# SCH_Andrew_s-NFC-Card_2024-04-21.net
KiCad netlist of a schematic drawn in EasyEDA
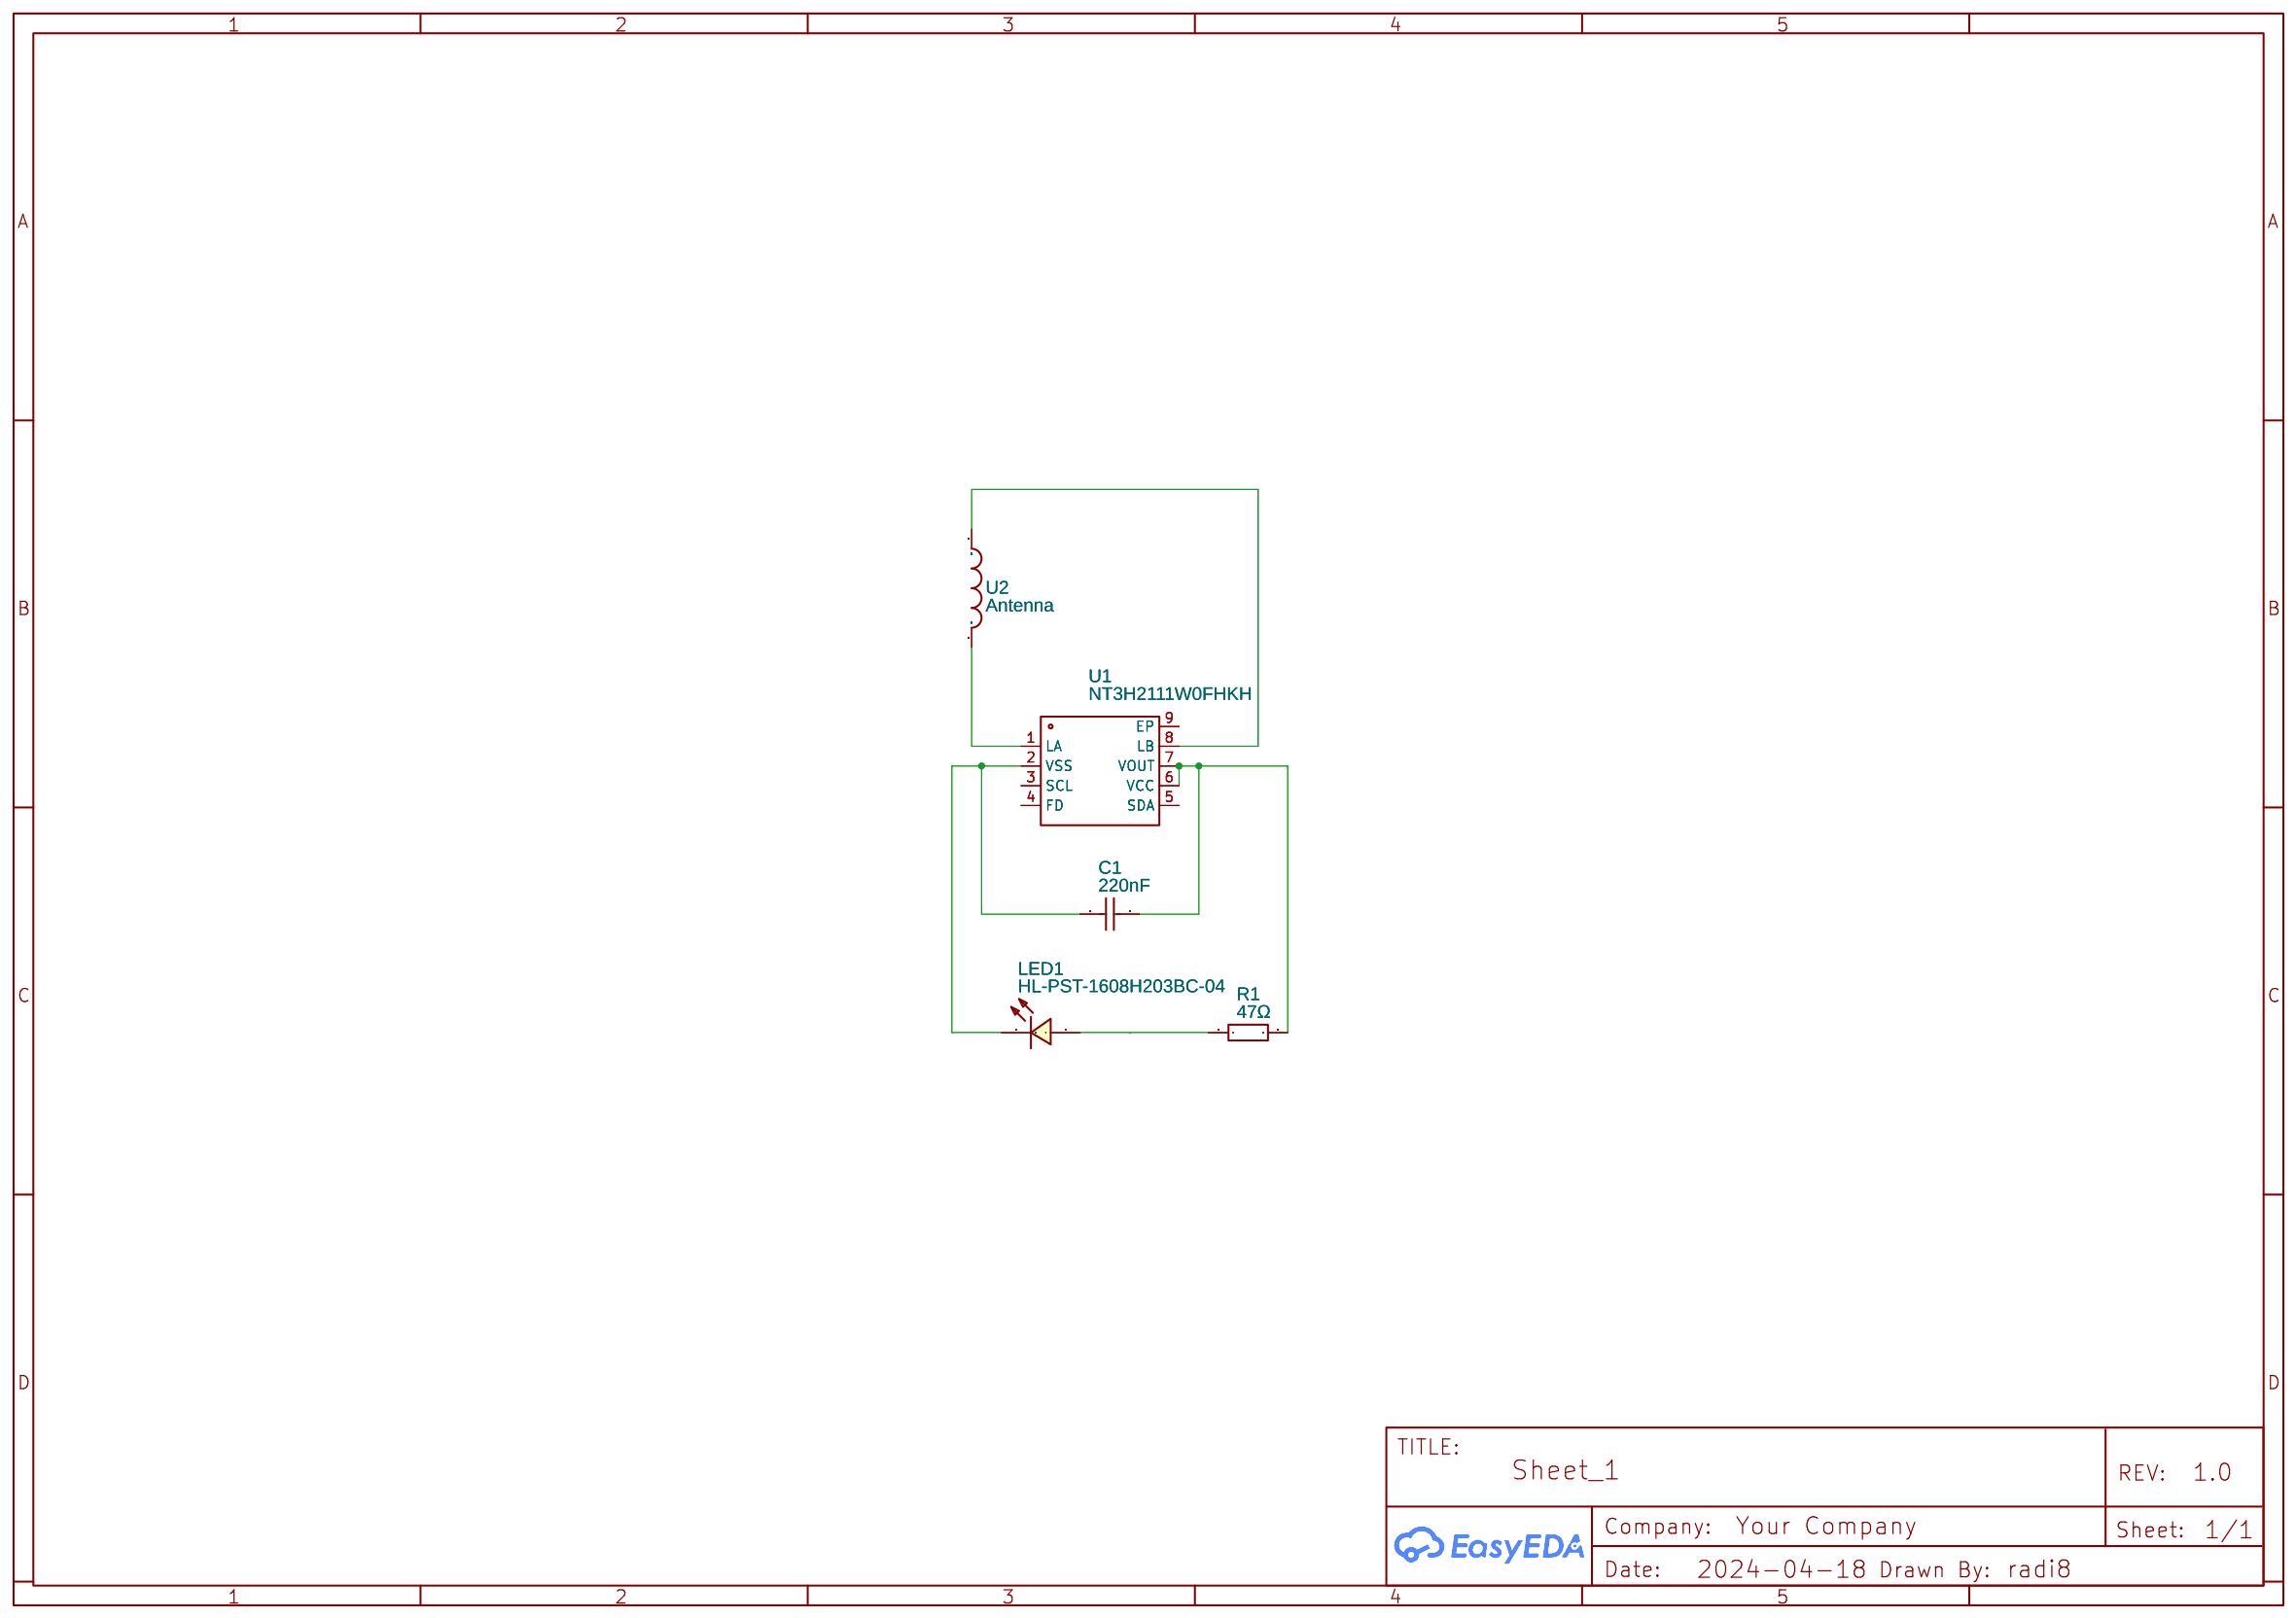
[diagram p0: schematic sheet]

(export (version "E")
  (design (tool "Eeschema 10.0.6"))
  (components
    (comp (ref "C1")
      (value "220nF")
      (fields
        (field (name "Manufacturer Part") "CL10B224KA8NNNC")
        (field (name "Manufacturer") "SAMSUNG(三星)")
      )
      (libsource (lib "") (part "CL10B224KA8NNNC"))
    )
    (comp (ref "LED1")
      (value "HL-PST-1608H203BC-04")
      (fields (field (name "Manufacturer") "HONGLITRONIC(鸿利光电)"))
      (libsource (lib "") (part "HL-PST-1608H203BC-04"))
    )
    (comp (ref "R1")
      (value "47Ω")
      (fields
        (field (name "Manufacturer Part") "0603WAF470JT5E")
        (field (name "Manufacturer") "UNI-ROYAL(厚声)")
      )
      (libsource (lib "") (part "0603WAF470JT5E"))
    )
    (comp (ref "U1")
      (value "NT3H2111W0FHKH")
      (fields (field (name "Manufacturer") "NXP(恩智浦)"))
      (libsource (lib "") (part "NT3H2111W0FHKH"))
    )
    (comp (ref "U2") (value "Antenna") (libsource (lib "") (part "Antenna")))
  )
  (nets
    (net (code "1") (name "Net-(LED1-A)") (class "Default")
      (node (ref "LED1") (pin "2") (pinfunction "A_2") (pintype "unspecified"))
      (node (ref "R1") (pin "1") (pinfunction "1_1") (pintype "input"))
    )
    (net (code "2") (name "Net-(LED1-C)") (class "Default")
      (node (ref "C1") (pin "1") (pinfunction "1_1") (pintype "input"))
      (node (ref "LED1") (pin "1") (pinfunction "C_1") (pintype "unspecified"))
      (node (ref "U1") (pin "2") (pinfunction "VSS_2") (pintype "unspecified"))
    )
    (net (code "3") (name "Net-(U1-LA)") (class "Default")
      (node (ref "U1") (pin "1") (pinfunction "LA_1") (pintype "unspecified"))
      (node (ref "U2") (pin "P$1") (pinfunction "P$1_P$1") (pintype "unspecified"))
    )
    (net (code "4") (name "Net-(U1-LB)") (class "Default")
      (node (ref "U1") (pin "8") (pinfunction "LB_8") (pintype "unspecified"))
      (node (ref "U2") (pin "P$2") (pinfunction "P$2_P$2") (pintype "unspecified"))
    )
    (net (code "5") (name "Net-(U1-VCC)") (class "Default")
      (node (ref "C1") (pin "2") (pinfunction "2_2") (pintype "input"))
      (node (ref "R1") (pin "2") (pinfunction "2_2") (pintype "input"))
      (node (ref "U1") (pin "6") (pinfunction "VCC_6") (pintype "unspecified"))
      (node (ref "U1") (pin "7") (pinfunction "VOUT_7") (pintype "unspecified"))
    )
    (net (code "6") (name "unconnected-(U1-EP-Pad9)") (class "Default")
      (node (ref "U1") (pin "9") (pinfunction "EP_9") (pintype "unspecified"))
    )
    (net (code "7") (name "unconnected-(U1-FD-Pad4)") (class "Default")
      (node (ref "U1") (pin "4") (pinfunction "FD_4") (pintype "unspecified"))
    )
    (net (code "8") (name "unconnected-(U1-SCL-Pad3)") (class "Default")
      (node (ref "U1") (pin "3") (pinfunction "SCL_3") (pintype "unspecified"))
    )
    (net (code "9") (name "unconnected-(U1-SDA-Pad5)") (class "Default")
      (node (ref "U1") (pin "5") (pinfunction "SDA_5") (pintype "unspecified"))
    )
  )
)
